# ring-modulator-v1_1.net
KiCad netlist of a schematic drawn in EAGLE
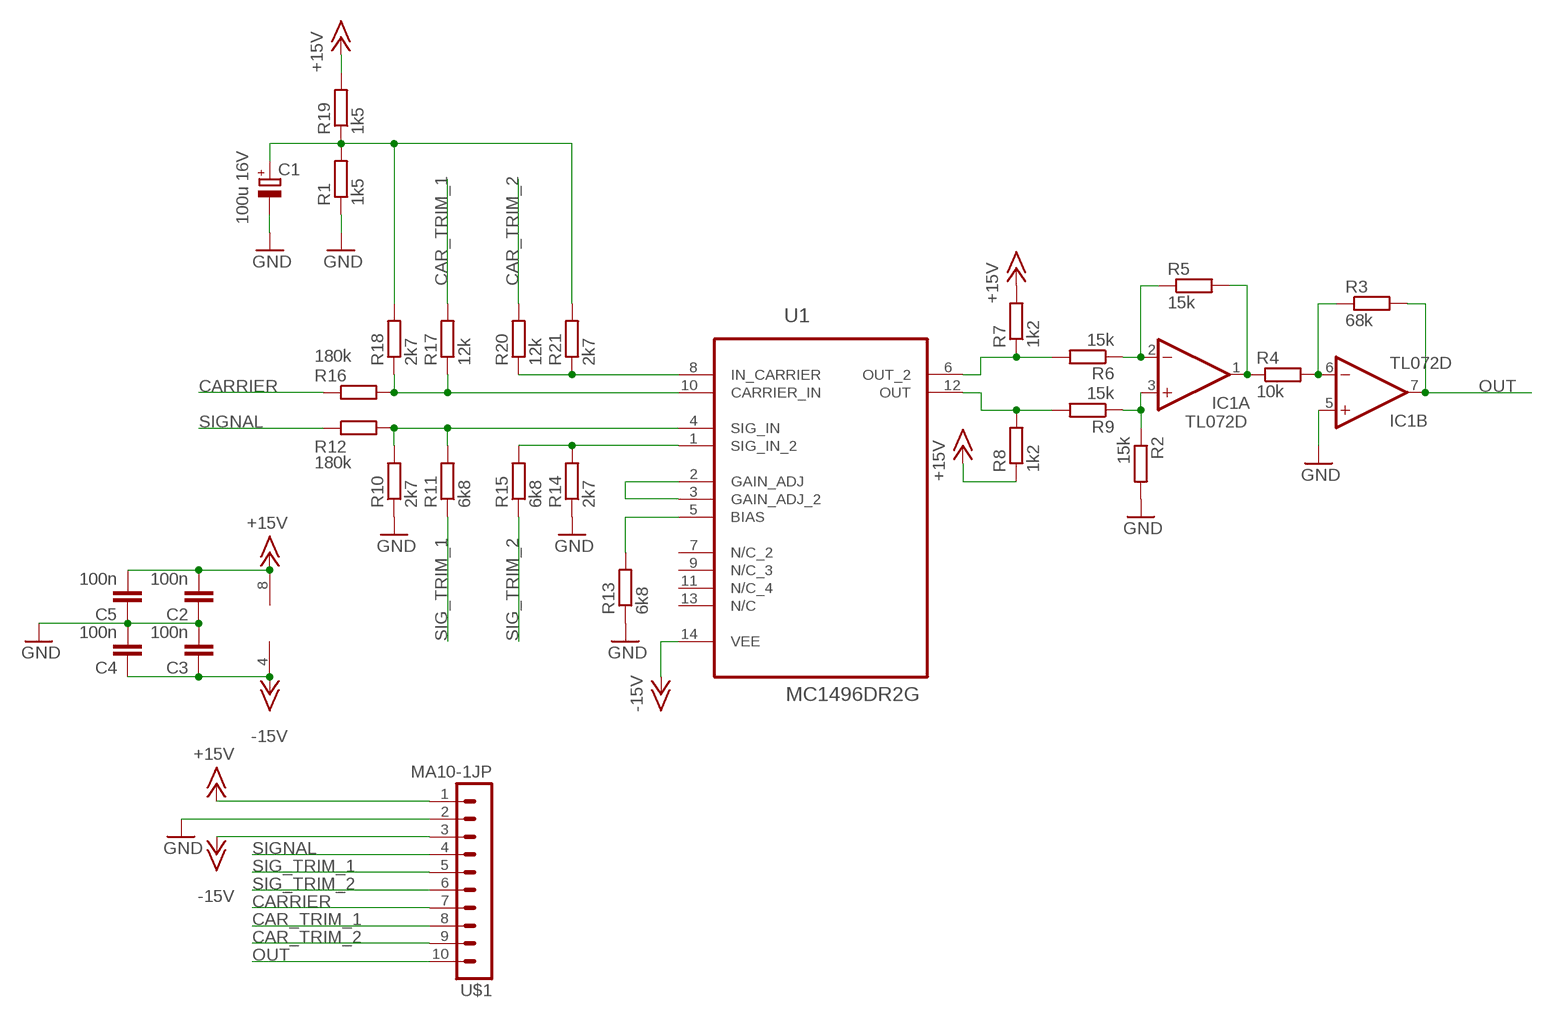
[diagram p0: schematic, sheet 1]

(export (version "E")
  (design (tool "Eeschema 10.0.6"))
  (components
    (comp (ref "C1")
      (value "100u 16V")
      (footprint "eagle-import:E2,5-5")
      (libsource (lib "eagle-import") (part "CPOL-EUE2.5-5"))
    )
    (comp (ref "C2")
      (value "100n")
      (footprint "eagle-import:C0805")
      (libsource (lib "eagle-import") (part "C-EUC0805"))
    )
    (comp (ref "C3")
      (value "100n")
      (footprint "eagle-import:C0805")
      (libsource (lib "eagle-import") (part "C-EUC0805"))
    )
    (comp (ref "C4")
      (value "100n")
      (footprint "eagle-import:C0805")
      (libsource (lib "eagle-import") (part "C-EUC0805"))
    )
    (comp (ref "C5")
      (value "100n")
      (footprint "eagle-import:C0805")
      (libsource (lib "eagle-import") (part "C-EUC0805"))
    )
    (comp (ref "IC1")
      (value "TL072D")
      (footprint "eagle-import:SO08J")
      (libsource (lib "eagle-import") (part "TL072D"))
    )
    (comp (ref "R1")
      (value "1k5")
      (footprint "eagle-import:R0805")
      (libsource (lib "eagle-import") (part "R-EU_R0805"))
    )
    (comp (ref "R2")
      (value "15k")
      (footprint "eagle-import:R0805")
      (libsource (lib "eagle-import") (part "R-EU_R0805"))
    )
    (comp (ref "R3")
      (value "68k")
      (footprint "eagle-import:R0805")
      (libsource (lib "eagle-import") (part "R-EU_R0805"))
    )
    (comp (ref "R4")
      (value "10k")
      (footprint "eagle-import:R0805")
      (libsource (lib "eagle-import") (part "R-EU_R0805"))
    )
    (comp (ref "R5")
      (value "15k")
      (footprint "eagle-import:R0805")
      (libsource (lib "eagle-import") (part "R-EU_R0805"))
    )
    (comp (ref "R6")
      (value "15k")
      (footprint "eagle-import:R0805")
      (libsource (lib "eagle-import") (part "R-EU_R0805"))
    )
    (comp (ref "R7")
      (value "1k2")
      (footprint "eagle-import:R0805")
      (libsource (lib "eagle-import") (part "R-EU_R0805"))
    )
    (comp (ref "R8")
      (value "1k2")
      (footprint "eagle-import:R0805")
      (libsource (lib "eagle-import") (part "R-EU_R0805"))
    )
    (comp (ref "R9")
      (value "15k")
      (footprint "eagle-import:R0805")
      (libsource (lib "eagle-import") (part "R-EU_R0805"))
    )
    (comp (ref "R10")
      (value "2k7")
      (footprint "eagle-import:R0805")
      (libsource (lib "eagle-import") (part "R-EU_R0805"))
    )
    (comp (ref "R11")
      (value "6k8")
      (footprint "eagle-import:R0805")
      (libsource (lib "eagle-import") (part "R-EU_R0805"))
    )
    (comp (ref "R12")
      (value "180k")
      (footprint "eagle-import:R0805")
      (libsource (lib "eagle-import") (part "R-EU_R0805"))
    )
    (comp (ref "R13")
      (value "6k8")
      (footprint "eagle-import:R0805")
      (libsource (lib "eagle-import") (part "R-EU_R0805"))
    )
    (comp (ref "R14")
      (value "2k7")
      (footprint "eagle-import:R0805")
      (libsource (lib "eagle-import") (part "R-EU_R0805"))
    )
    (comp (ref "R15")
      (value "6k8")
      (footprint "eagle-import:R0805")
      (libsource (lib "eagle-import") (part "R-EU_R0805"))
    )
    (comp (ref "R16")
      (value "180k")
      (footprint "eagle-import:R0805")
      (libsource (lib "eagle-import") (part "R-EU_R0805"))
    )
    (comp (ref "R17")
      (value "12k")
      (footprint "eagle-import:R0805")
      (libsource (lib "eagle-import") (part "R-EU_R0805"))
    )
    (comp (ref "R18")
      (value "2k7")
      (footprint "eagle-import:R0805")
      (libsource (lib "eagle-import") (part "R-EU_R0805"))
    )
    (comp (ref "R19")
      (value "1k5")
      (footprint "eagle-import:R0805")
      (libsource (lib "eagle-import") (part "R-EU_R0805"))
    )
    (comp (ref "R20")
      (value "12k")
      (footprint "eagle-import:R0805")
      (libsource (lib "eagle-import") (part "R-EU_R0805"))
    )
    (comp (ref "R21")
      (value "2k7")
      (footprint "eagle-import:R0805")
      (libsource (lib "eagle-import") (part "R-EU_R0805"))
    )
    (comp (ref "U$1")
      (value "MA10-1JP")
      (footprint "eagle-import:SIP-PIN10-1J")
      (libsource (lib "eagle-import") (part "MA10-1JP"))
    )
    (comp (ref "U1")
      (value "MC1496DR2G")
      (footprint "eagle-import:SOIC127P600X175-14N")
      (libsource (lib "eagle-import") (part "MC1496DR2G"))
    )
  )
  (nets
    (net (code "1") (name "+15V") (class "Default")
      (node (ref "C2") (pin "2") (pinfunction "2_2") (pintype "passive"))
      (node (ref "C5") (pin "2") (pinfunction "2_2") (pintype "passive"))
      (node (ref "IC1") (pin "8") (pinfunction "V+_8") (pintype "power_in"))
      (node (ref "R19") (pin "2") (pinfunction "2_2") (pintype "passive"))
      (node (ref "R7") (pin "2") (pinfunction "2_2") (pintype "passive"))
      (node (ref "R8") (pin "1") (pinfunction "1_1") (pintype "passive"))
      (node (ref "U$1") (pin "1") (pinfunction "1_1") (pintype "passive"))
    )
    (net (code "2") (name "-15V") (class "Default")
      (node (ref "C3") (pin "1") (pinfunction "1_1") (pintype "passive"))
      (node (ref "C4") (pin "1") (pinfunction "1_1") (pintype "passive"))
      (node (ref "IC1") (pin "4") (pinfunction "V-_4") (pintype "power_in"))
      (node (ref "U$1") (pin "3") (pinfunction "3_3") (pintype "passive"))
      (node (ref "U1") (pin "14") (pinfunction "VEE_14") (pintype "passive"))
    )
    (net (code "3") (name "/CARRIER") (class "Default")
      (node (ref "R16") (pin "1") (pinfunction "1_1") (pintype "passive"))
      (node (ref "U$1") (pin "7") (pinfunction "7_7") (pintype "passive"))
    )
    (net (code "4") (name "/CAR_TRIM_1") (class "Default")
      (node (ref "R17") (pin "2") (pinfunction "2_2") (pintype "passive"))
      (node (ref "U$1") (pin "8") (pinfunction "8_8") (pintype "passive"))
    )
    (net (code "5") (name "/CAR_TRIM_2") (class "Default")
      (node (ref "R20") (pin "2") (pinfunction "2_2") (pintype "passive"))
      (node (ref "U$1") (pin "9") (pinfunction "9_9") (pintype "passive"))
    )
    (net (code "6") (name "/OUT") (class "Default")
      (node (ref "IC1") (pin "7") (pinfunction "OUT_7") (pintype "output"))
      (node (ref "R3") (pin "2") (pinfunction "2_2") (pintype "passive"))
      (node (ref "U$1") (pin "10") (pinfunction "10_10") (pintype "passive"))
    )
    (net (code "7") (name "/SIGNAL") (class "Default")
      (node (ref "R12") (pin "1") (pinfunction "1_1") (pintype "passive"))
      (node (ref "U$1") (pin "4") (pinfunction "4_4") (pintype "passive"))
    )
    (net (code "8") (name "/SIG_TRIM_1") (class "Default")
      (node (ref "R11") (pin "1") (pinfunction "1_1") (pintype "passive"))
      (node (ref "U$1") (pin "5") (pinfunction "5_5") (pintype "passive"))
    )
    (net (code "9") (name "/SIG_TRIM_2") (class "Default")
      (node (ref "R15") (pin "1") (pinfunction "1_1") (pintype "passive"))
      (node (ref "U$1") (pin "6") (pinfunction "6_6") (pintype "passive"))
    )
    (net (code "10") (name "GND") (class "Default")
      (node (ref "C1") (pin "-") (pinfunction "-_-") (pintype "passive"))
      (node (ref "C2") (pin "1") (pinfunction "1_1") (pintype "passive"))
      (node (ref "C3") (pin "2") (pinfunction "2_2") (pintype "passive"))
      (node (ref "C4") (pin "2") (pinfunction "2_2") (pintype "passive"))
      (node (ref "C5") (pin "1") (pinfunction "1_1") (pintype "passive"))
      (node (ref "IC1") (pin "5") (pinfunction "+IN_5") (pintype "input"))
      (node (ref "R1") (pin "1") (pinfunction "1_1") (pintype "passive"))
      (node (ref "R10") (pin "1") (pinfunction "1_1") (pintype "passive"))
      (node (ref "R13") (pin "1") (pinfunction "1_1") (pintype "passive"))
      (node (ref "R14") (pin "1") (pinfunction "1_1") (pintype "passive"))
      (node (ref "R2") (pin "2") (pinfunction "2_2") (pintype "passive"))
      (node (ref "U$1") (pin "2") (pinfunction "2_2") (pintype "passive"))
    )
    (net (code "11") (name "Net-(C1-Pad+)") (class "Default")
      (node (ref "C1") (pin "+") (pinfunction "+_+") (pintype "passive"))
      (node (ref "R1") (pin "2") (pinfunction "2_2") (pintype "passive"))
      (node (ref "R18") (pin "2") (pinfunction "2_2") (pintype "passive"))
      (node (ref "R19") (pin "1") (pinfunction "1_1") (pintype "passive"))
      (node (ref "R21") (pin "2") (pinfunction "2_2") (pintype "passive"))
    )
    (net (code "12") (name "Net-(IC1A-+IN)") (class "Default")
      (node (ref "IC1") (pin "3") (pinfunction "+IN_3") (pintype "input"))
      (node (ref "R2") (pin "1") (pinfunction "1_1") (pintype "passive"))
      (node (ref "R9") (pin "1") (pinfunction "1_1") (pintype "passive"))
    )
    (net (code "13") (name "Net-(IC1A--IN)") (class "Default")
      (node (ref "IC1") (pin "2") (pinfunction "-IN_2") (pintype "input"))
      (node (ref "R5") (pin "1") (pinfunction "1_1") (pintype "passive"))
      (node (ref "R6") (pin "1") (pinfunction "1_1") (pintype "passive"))
    )
    (net (code "14") (name "Net-(IC1A-OUT)") (class "Default")
      (node (ref "IC1") (pin "1") (pinfunction "OUT_1") (pintype "output"))
      (node (ref "R4") (pin "1") (pinfunction "1_1") (pintype "passive"))
      (node (ref "R5") (pin "2") (pinfunction "2_2") (pintype "passive"))
    )
    (net (code "15") (name "Net-(IC1B--IN)") (class "Default")
      (node (ref "IC1") (pin "6") (pinfunction "-IN_6") (pintype "input"))
      (node (ref "R3") (pin "1") (pinfunction "1_1") (pintype "passive"))
      (node (ref "R4") (pin "2") (pinfunction "2_2") (pintype "passive"))
    )
    (net (code "16") (name "Net-(U1-BIAS)") (class "Default")
      (node (ref "R13") (pin "2") (pinfunction "2_2") (pintype "passive"))
      (node (ref "U1") (pin "5") (pinfunction "BIAS_5") (pintype "input"))
    )
    (net (code "17") (name "Net-(U1-CARRIER_IN)") (class "Default")
      (node (ref "R16") (pin "2") (pinfunction "2_2") (pintype "passive"))
      (node (ref "R17") (pin "1") (pinfunction "1_1") (pintype "passive"))
      (node (ref "R18") (pin "1") (pinfunction "1_1") (pintype "passive"))
      (node (ref "U1") (pin "10") (pinfunction "CARRIER_IN_10") (pintype "power_in"))
    )
    (net (code "18") (name "Net-(U1-GAIN_ADJ)") (class "Default")
      (node (ref "U1") (pin "2") (pinfunction "GAIN_ADJ_2") (pintype "input"))
      (node (ref "U1") (pin "3") (pinfunction "GAIN_ADJ_2_3") (pintype "input"))
    )
    (net (code "19") (name "Net-(U1-IN_CARRIER)") (class "Default")
      (node (ref "R20") (pin "1") (pinfunction "1_1") (pintype "passive"))
      (node (ref "R21") (pin "1") (pinfunction "1_1") (pintype "passive"))
      (node (ref "U1") (pin "8") (pinfunction "IN_CARRIER_8") (pintype "power_in"))
    )
    (net (code "20") (name "Net-(U1-OUT)") (class "Default")
      (node (ref "R8") (pin "2") (pinfunction "2_2") (pintype "passive"))
      (node (ref "R9") (pin "2") (pinfunction "2_2") (pintype "passive"))
      (node (ref "U1") (pin "12") (pinfunction "OUT_12") (pintype "output"))
    )
    (net (code "21") (name "Net-(U1-OUT_2)") (class "Default")
      (node (ref "R6") (pin "2") (pinfunction "2_2") (pintype "passive"))
      (node (ref "R7") (pin "1") (pinfunction "1_1") (pintype "passive"))
      (node (ref "U1") (pin "6") (pinfunction "OUT_2_6") (pintype "output"))
    )
    (net (code "22") (name "Net-(U1-SIG_IN)") (class "Default")
      (node (ref "R10") (pin "2") (pinfunction "2_2") (pintype "passive"))
      (node (ref "R11") (pin "2") (pinfunction "2_2") (pintype "passive"))
      (node (ref "R12") (pin "2") (pinfunction "2_2") (pintype "passive"))
      (node (ref "U1") (pin "4") (pinfunction "SIG_IN_4") (pintype "input"))
    )
    (net (code "23") (name "Net-(U1-SIG_IN_2)") (class "Default")
      (node (ref "R14") (pin "2") (pinfunction "2_2") (pintype "passive"))
      (node (ref "R15") (pin "2") (pinfunction "2_2") (pintype "passive"))
      (node (ref "U1") (pin "1") (pinfunction "SIG_IN_2_1") (pintype "input"))
    )
    (net (code "24") (name "unconnected-(U1-N{slash}C-Pad13)") (class "Default")
      (node (ref "U1") (pin "13") (pinfunction "N/C_13") (pintype "no_connect"))
    )
    (net (code "25") (name "unconnected-(U1-N{slash}C_2-Pad7)") (class "Default")
      (node (ref "U1") (pin "7") (pinfunction "N/C_2_7") (pintype "no_connect"))
    )
    (net (code "26") (name "unconnected-(U1-N{slash}C_3-Pad9)") (class "Default")
      (node (ref "U1") (pin "9") (pinfunction "N/C_3_9") (pintype "no_connect"))
    )
    (net (code "27") (name "unconnected-(U1-N{slash}C_4-Pad11)") (class "Default")
      (node (ref "U1") (pin "11") (pinfunction "N/C_4_11") (pintype "no_connect"))
    )
  )
)
